# SparkFun_MPU-9250_Breakout.net
KiCad netlist of a schematic drawn in EAGLE
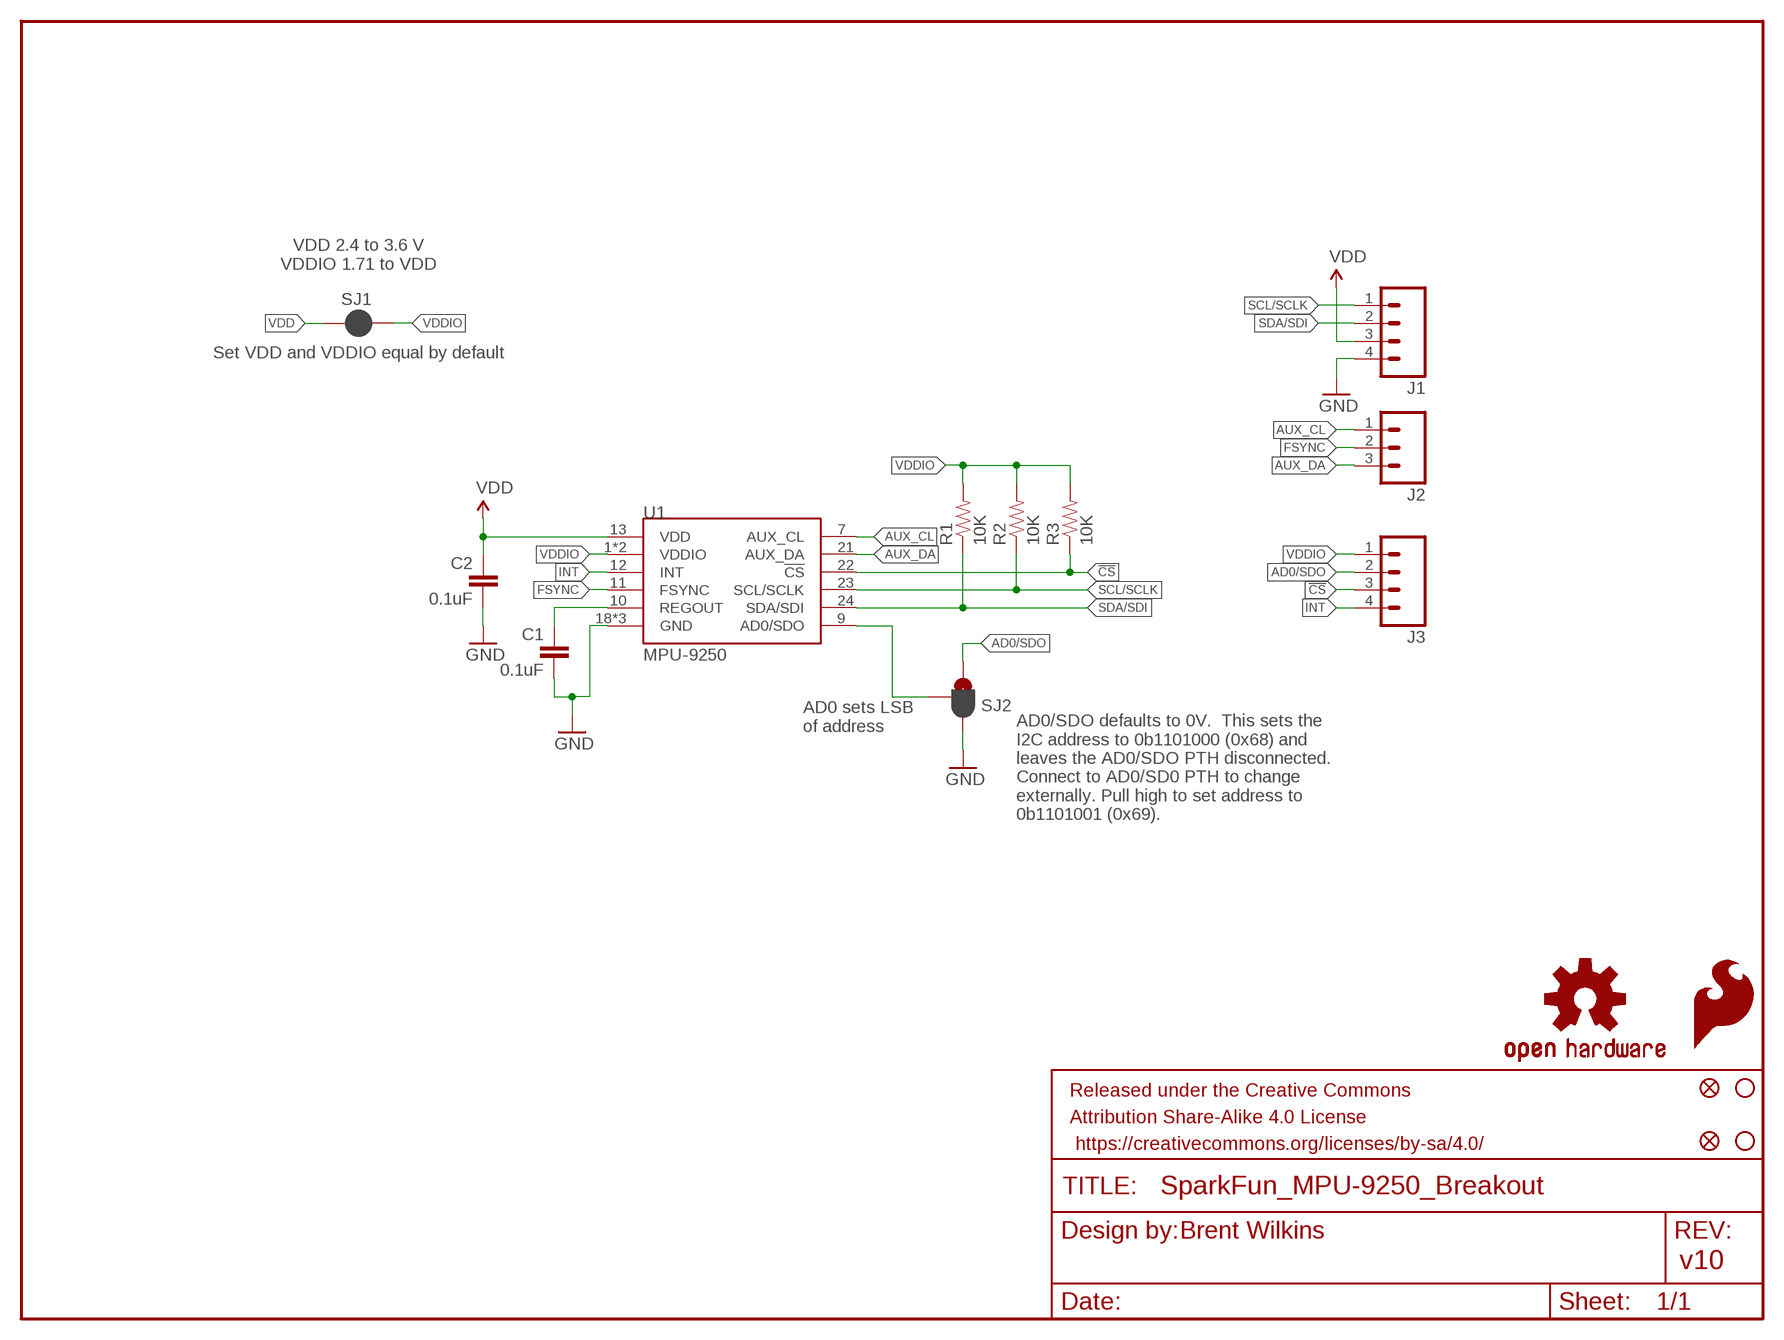
[diagram p0: schematic, sheet 1]

(export (version "E")
  (design (tool "Eeschema 10.0.6"))
  (components
    (comp (ref "C1")
      (value "0.1uF")
      (footprint "eagle-import:0603-CAP")
      (libsource (lib "eagle-import") (part "0.1UF-25V(+80/-20%)(0603)"))
    )
    (comp (ref "C2")
      (value "0.1uF")
      (footprint "eagle-import:0603-CAP")
      (libsource (lib "eagle-import") (part "0.1UF-25V(+80/-20%)(0603)"))
    )
    (comp (ref "FID1")
      (value "FIDUCIAL1X2")
      (footprint "eagle-import:FIDUCIAL-1X2")
      (libsource (lib "eagle-import") (part "FIDUCIAL1X2"))
    )
    (comp (ref "FID2")
      (value "FIDUCIAL1X2")
      (footprint "eagle-import:FIDUCIAL-1X2")
      (libsource (lib "eagle-import") (part "FIDUCIAL1X2"))
    )
    (comp (ref "FRAME1")
      (value "FRAME-LETTER")
      (footprint "eagle-import:CREATIVE_COMMONS")
      (libsource (lib "eagle-import") (part "FRAME-LETTER"))
    )
    (comp (ref "J1")
      (value "M04PTH")
      (footprint "eagle-import:1X04")
      (libsource (lib "eagle-import") (part "M04PTH"))
    )
    (comp (ref "J2")
      (value "M03PTH")
      (footprint "eagle-import:1X03")
      (libsource (lib "eagle-import") (part "M03PTH"))
    )
    (comp (ref "J3")
      (value "M04PTH")
      (footprint "eagle-import:1X04")
      (libsource (lib "eagle-import") (part "M04PTH"))
    )
    (comp (ref "LOGO1")
      (value "SFE_LOGO_FLAME.1_INCH")
      (footprint "eagle-import:SFE_LOGO_FLAME_.1")
      (libsource (lib "eagle-import") (part "SFE_LOGO_FLAME.1_INCH"))
    )
    (comp (ref "LOGO2")
      (value "OSHW-LOGOS")
      (footprint "eagle-import:OSHW-LOGO-S")
      (libsource (lib "eagle-import") (part "OSHW-LOGOS"))
    )
    (comp (ref "R1")
      (value "10K")
      (footprint "eagle-import:0603-RES")
      (libsource (lib "eagle-import") (part "10KOHM-1/10W-1%(0603)0603"))
    )
    (comp (ref "R2")
      (value "10K")
      (footprint "eagle-import:0603-RES")
      (libsource (lib "eagle-import") (part "10KOHM-1/10W-1%(0603)0603"))
    )
    (comp (ref "R3")
      (value "10K")
      (footprint "eagle-import:0603-RES")
      (libsource (lib "eagle-import") (part "10KOHM-1/10W-1%(0603)0603"))
    )
    (comp (ref "SJ1")
      (value "JUMPER-PAD-2-NC_BY_PASTEFULL-BOX-SILK")
      (footprint "eagle-import:PAD-JUMPER-2-NC_BY_PASTE_YES_SILK_FULL_BOX")
      (libsource (lib "eagle-import") (part "JUMPER-PAD-2-NC_BY_PASTEFULL-BOX-SILK"))
    )
    (comp (ref "SJ2")
      (value "JUMPER_PAD-3-1&2_NC_BY_PASTE")
      (footprint "eagle-import:PAD-HUMPER-3-1&2_NC_BY_PASTE_YES_SILK_FULL_BOX")
      (libsource (lib "eagle-import") (part "JUMPER_PAD-3-1&2_NC_BY_PASTE"))
    )
    (comp (ref "STANDOFF1")
      (value "STAND-OFF")
      (footprint "eagle-import:STAND-OFF")
      (libsource (lib "eagle-import") (part "STAND-OFF"))
    )
    (comp (ref "STANDOFF2")
      (value "STAND-OFF")
      (footprint "eagle-import:STAND-OFF")
      (libsource (lib "eagle-import") (part "STAND-OFF"))
    )
    (comp (ref "U1")
      (value "MPU-9250")
      (footprint "eagle-import:QFN24_PAD")
      (libsource (lib "eagle-import") (part "MPU-9250"))
    )
  )
  (nets
    (net (code "1") (name "/~{CS}") (class "Default")
      (node (ref "J3") (pin "3") (pinfunction "3_3") (pintype "passive"))
      (node (ref "R3") (pin "1") (pinfunction "1_1") (pintype "passive"))
      (node (ref "U1") (pin "22") (pinfunction "~{CS}_22") (pintype "bidirectional"))
    )
    (net (code "2") (name "AD0{slash}SDO") (class "Default")
      (node (ref "J3") (pin "2") (pinfunction "2_2") (pintype "passive"))
      (node (ref "SJ2") (pin "3") (pinfunction "3_3") (pintype "passive"))
    )
    (net (code "3") (name "AUX_CL") (class "Default")
      (node (ref "J2") (pin "1") (pinfunction "1_1") (pintype "passive"))
      (node (ref "U1") (pin "7") (pinfunction "AUX_CL_7") (pintype "bidirectional"))
    )
    (net (code "4") (name "AUX_DA") (class "Default")
      (node (ref "J2") (pin "3") (pinfunction "3_3") (pintype "passive"))
      (node (ref "U1") (pin "21") (pinfunction "AUX_DA_21") (pintype "bidirectional"))
    )
    (net (code "5") (name "FSYNC") (class "Default")
      (node (ref "J2") (pin "2") (pinfunction "2_2") (pintype "passive"))
      (node (ref "U1") (pin "11") (pinfunction "FSYNC_11") (pintype "bidirectional"))
    )
    (net (code "6") (name "GND") (class "Default")
      (node (ref "C1") (pin "2") (pinfunction "2_2") (pintype "passive"))
      (node (ref "C2") (pin "2") (pinfunction "2_2") (pintype "passive"))
      (node (ref "J1") (pin "4") (pinfunction "4_4") (pintype "passive"))
      (node (ref "SJ2") (pin "1") (pinfunction "1_1") (pintype "passive"))
      (node (ref "U1") (pin "18") (pinfunction "GND_18") (pintype "bidirectional"))
      (node (ref "U1") (pin "20") (pinfunction "GND_20") (pintype "bidirectional"))
      (node (ref "U1") (pin "CENTER") (pinfunction "GND_CENTER") (pintype "bidirectional"))
    )
    (net (code "7") (name "INT") (class "Default")
      (node (ref "J3") (pin "4") (pinfunction "4_4") (pintype "passive"))
      (node (ref "U1") (pin "12") (pinfunction "INT_12") (pintype "bidirectional"))
    )
    (net (code "8") (name "Net-(U1-AD0{slash}SDO)") (class "Default")
      (node (ref "SJ2") (pin "2") (pinfunction "2_2") (pintype "passive"))
      (node (ref "U1") (pin "9") (pinfunction "AD0/SDO_9") (pintype "bidirectional"))
    )
    (net (code "9") (name "Net-(U1-REGOUT)") (class "Default")
      (node (ref "C1") (pin "1") (pinfunction "1_1") (pintype "passive"))
      (node (ref "U1") (pin "10") (pinfunction "REGOUT_10") (pintype "bidirectional"))
    )
    (net (code "10") (name "SCL{slash}SCLK") (class "Default")
      (node (ref "J1") (pin "1") (pinfunction "1_1") (pintype "passive"))
      (node (ref "R2") (pin "1") (pinfunction "1_1") (pintype "passive"))
      (node (ref "U1") (pin "23") (pinfunction "SCL/SCLK_23") (pintype "bidirectional"))
    )
    (net (code "11") (name "SDA{slash}SDI") (class "Default")
      (node (ref "J1") (pin "2") (pinfunction "2_2") (pintype "passive"))
      (node (ref "R1") (pin "1") (pinfunction "1_1") (pintype "passive"))
      (node (ref "U1") (pin "24") (pinfunction "SDA/SDI_24") (pintype "bidirectional"))
    )
    (net (code "12") (name "VDD") (class "Default")
      (node (ref "C2") (pin "1") (pinfunction "1_1") (pintype "passive"))
      (node (ref "J1") (pin "3") (pinfunction "3_3") (pintype "passive"))
      (node (ref "SJ1") (pin "1") (pinfunction "1_1") (pintype "passive"))
      (node (ref "U1") (pin "13") (pinfunction "VDD_13") (pintype "bidirectional"))
    )
    (net (code "13") (name "VDDIO") (class "Default")
      (node (ref "J3") (pin "1") (pinfunction "1_1") (pintype "passive"))
      (node (ref "R1") (pin "2") (pinfunction "2_2") (pintype "passive"))
      (node (ref "R2") (pin "2") (pinfunction "2_2") (pintype "passive"))
      (node (ref "R3") (pin "2") (pinfunction "2_2") (pintype "passive"))
      (node (ref "SJ1") (pin "2") (pinfunction "2_2") (pintype "passive"))
      (node (ref "U1") (pin "1") (pinfunction "VDDIO_1") (pintype "bidirectional"))
      (node (ref "U1") (pin "8") (pinfunction "VDDIO_8") (pintype "bidirectional"))
    )
  )
)
